# LED-Project.net
KiCad netlist of a schematic drawn in EAGLE
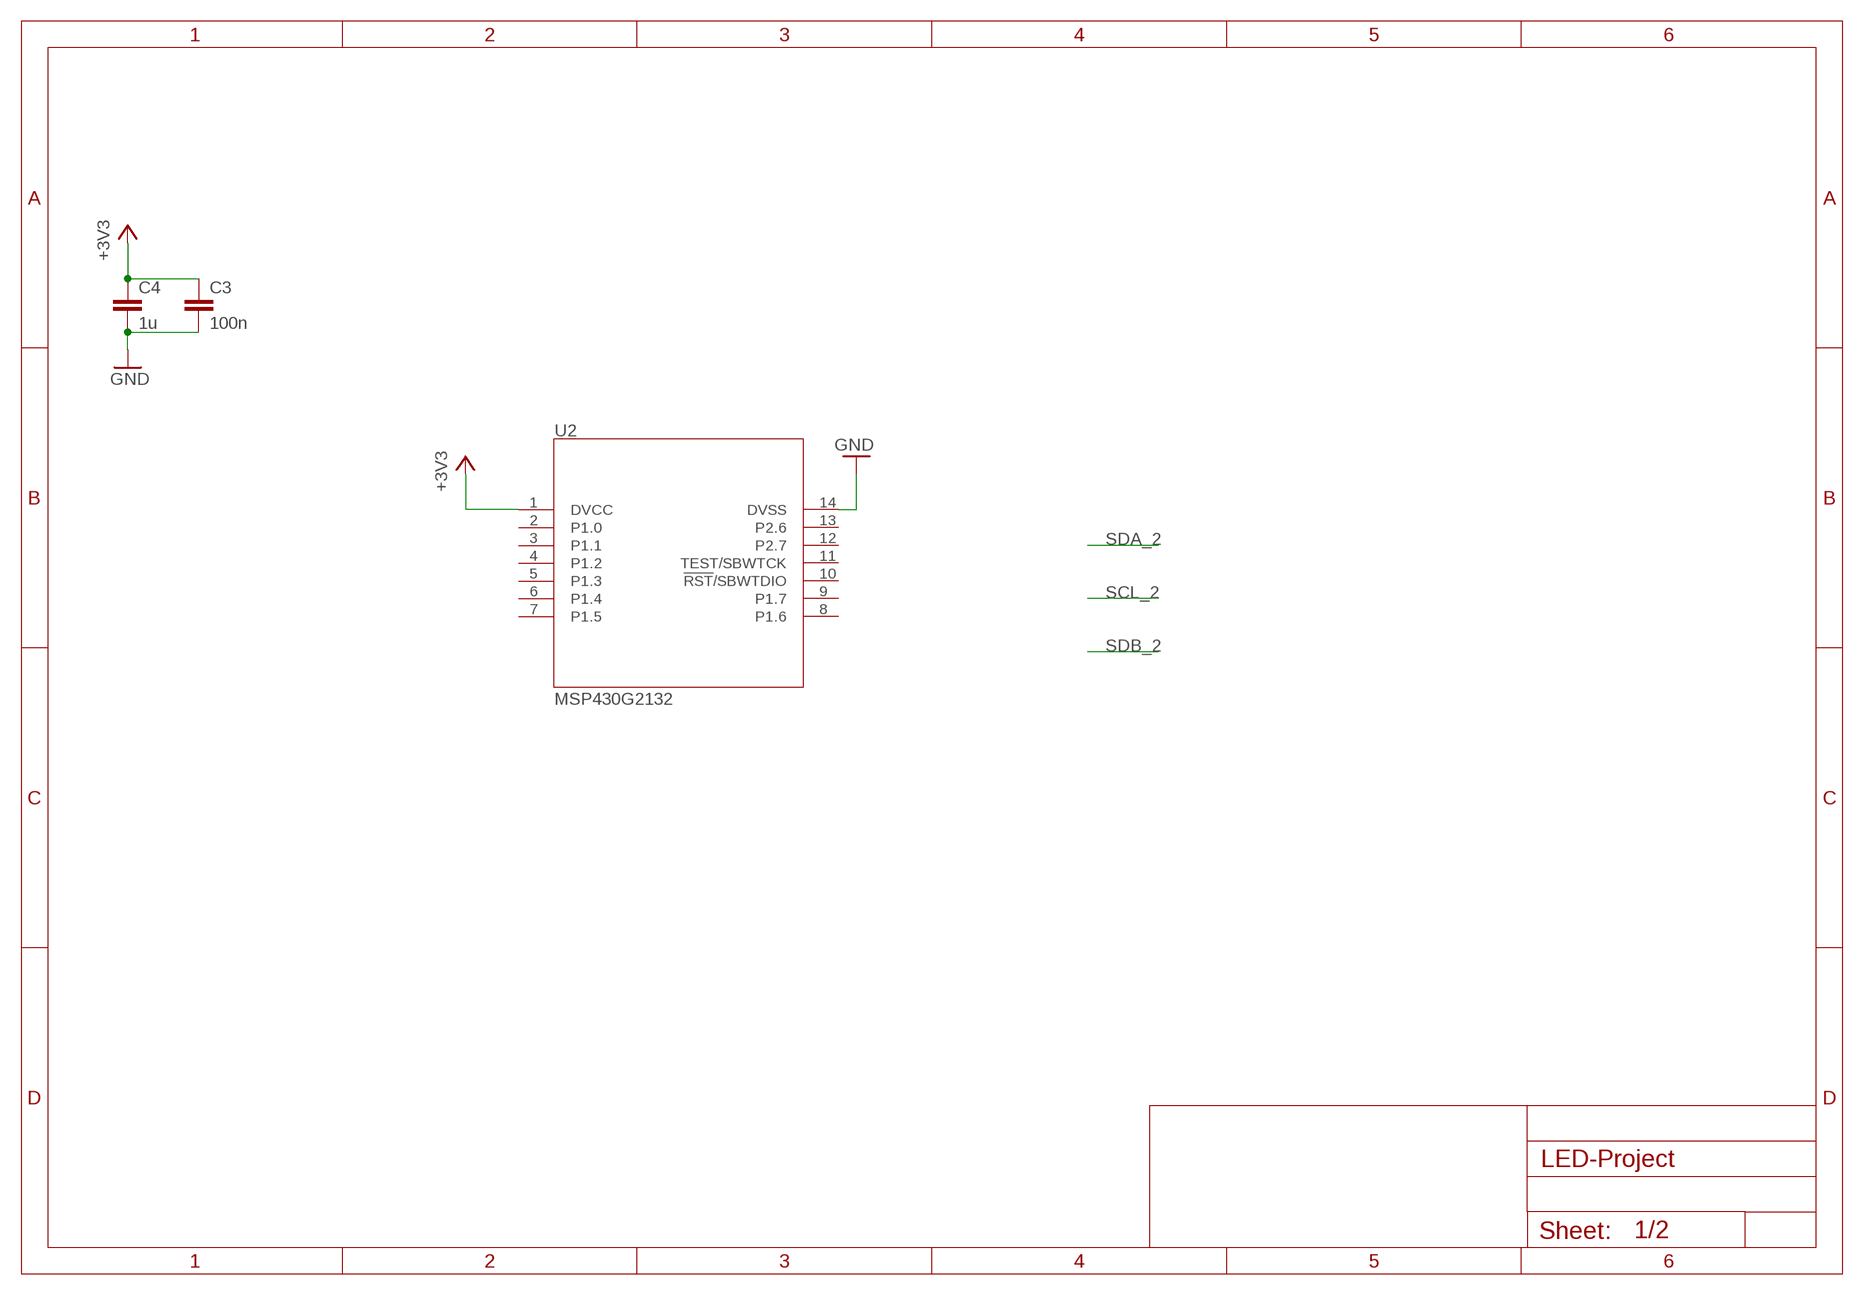
[diagram p0: schematic, sheet 1]
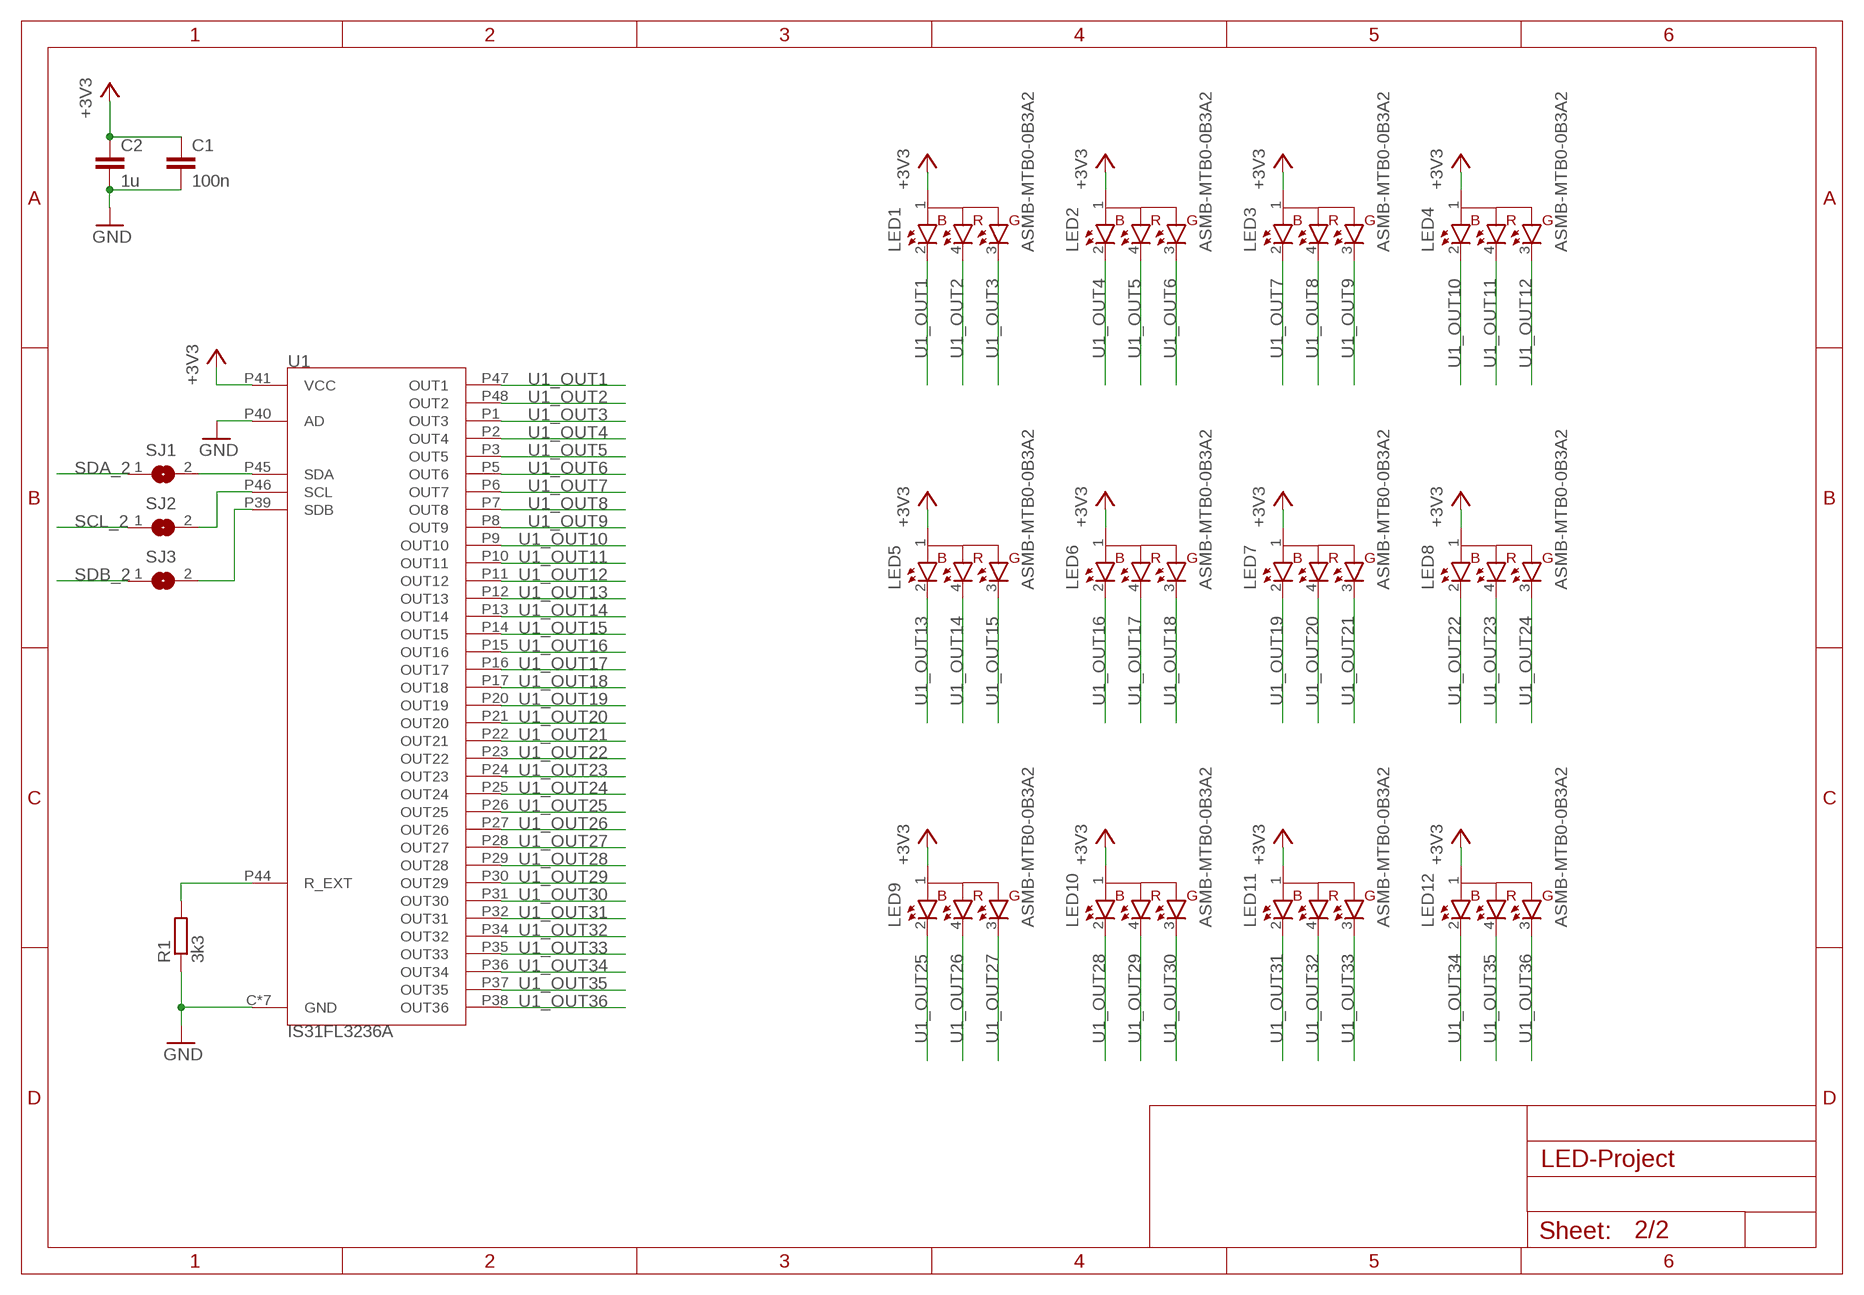
[diagram p1: schematic, sheet 2]

(export (version "E")
  (design (tool "Eeschema 10.0.6"))
  (components
    (comp (ref "C1")
      (value "100n")
      (footprint "eagle-import:C0805")
      (libsource (lib "eagle-import") (part "C-EUC0805"))
    )
    (comp (ref "C2")
      (value "1u")
      (footprint "eagle-import:C0805")
      (libsource (lib "eagle-import") (part "C-EUC0805"))
    )
    (comp (ref "LED1")
      (value "ASMB-MTB0-0B3A2")
      (footprint "eagle-import:LED-3.2-2.8")
      (libsource (lib "eagle-import") (part "ASMB-MTB0-0B3A2"))
    )
    (comp (ref "LED2")
      (value "ASMB-MTB0-0B3A2")
      (footprint "eagle-import:LED-3.2-2.8")
      (libsource (lib "eagle-import") (part "ASMB-MTB0-0B3A2"))
    )
    (comp (ref "LED3")
      (value "ASMB-MTB0-0B3A2")
      (footprint "eagle-import:LED-3.2-2.8")
      (libsource (lib "eagle-import") (part "ASMB-MTB0-0B3A2"))
    )
    (comp (ref "LED4")
      (value "ASMB-MTB0-0B3A2")
      (footprint "eagle-import:LED-3.2-2.8")
      (libsource (lib "eagle-import") (part "ASMB-MTB0-0B3A2"))
    )
    (comp (ref "LED5")
      (value "ASMB-MTB0-0B3A2")
      (footprint "eagle-import:LED-3.2-2.8")
      (libsource (lib "eagle-import") (part "ASMB-MTB0-0B3A2"))
    )
    (comp (ref "LED6")
      (value "ASMB-MTB0-0B3A2")
      (footprint "eagle-import:LED-3.2-2.8")
      (libsource (lib "eagle-import") (part "ASMB-MTB0-0B3A2"))
    )
    (comp (ref "LED7")
      (value "ASMB-MTB0-0B3A2")
      (footprint "eagle-import:LED-3.2-2.8")
      (libsource (lib "eagle-import") (part "ASMB-MTB0-0B3A2"))
    )
    (comp (ref "LED8")
      (value "ASMB-MTB0-0B3A2")
      (footprint "eagle-import:LED-3.2-2.8")
      (libsource (lib "eagle-import") (part "ASMB-MTB0-0B3A2"))
    )
    (comp (ref "LED9")
      (value "ASMB-MTB0-0B3A2")
      (footprint "eagle-import:LED-3.2-2.8")
      (libsource (lib "eagle-import") (part "ASMB-MTB0-0B3A2"))
    )
    (comp (ref "LED10")
      (value "ASMB-MTB0-0B3A2")
      (footprint "eagle-import:LED-3.2-2.8")
      (libsource (lib "eagle-import") (part "ASMB-MTB0-0B3A2"))
    )
    (comp (ref "LED11")
      (value "ASMB-MTB0-0B3A2")
      (footprint "eagle-import:LED-3.2-2.8")
      (libsource (lib "eagle-import") (part "ASMB-MTB0-0B3A2"))
    )
    (comp (ref "LED12")
      (value "ASMB-MTB0-0B3A2")
      (footprint "eagle-import:LED-3.2-2.8")
      (libsource (lib "eagle-import") (part "ASMB-MTB0-0B3A2"))
    )
    (comp (ref "R1")
      (value "3k3")
      (footprint "eagle-import:R0805")
      (libsource (lib "eagle-import") (part "R-EU_R0805"))
    )
    (comp (ref "SJ1") (value "SJ") (footprint "eagle-import:SJ") (libsource (lib "eagle-import") (part "SJ")))
    (comp (ref "SJ2") (value "SJ") (footprint "eagle-import:SJ") (libsource (lib "eagle-import") (part "SJ")))
    (comp (ref "SJ3") (value "SJ") (footprint "eagle-import:SJ") (libsource (lib "eagle-import") (part "SJ")))
    (comp (ref "U1")
      (value "IS31FL3236A")
      (footprint "eagle-import:ETQFP-48")
      (libsource (lib "eagle-import") (part "IS31FL3236A"))
    )
    (comp (ref "C3")
      (value "100n")
      (footprint "eagle-import:C0805")
      (libsource (lib "eagle-import") (part "C-EUC0805"))
    )
    (comp (ref "C4")
      (value "1u")
      (footprint "eagle-import:C0805")
      (libsource (lib "eagle-import") (part "C-EUC0805"))
    )
    (comp (ref "U2")
      (value "MSP430G2132")
      (footprint "eagle-import:TSSOP14")
      (libsource (lib "eagle-import") (part "MSP430G2132"))
    )
  )
  (nets
    (net (code "1") (name "+3V3") (class "Default")
      (node (ref "C1") (pin "1") (pinfunction "1_1") (pintype "passive"))
      (node (ref "C2") (pin "1") (pinfunction "1_1") (pintype "passive"))
      (node (ref "C3") (pin "1") (pinfunction "1_1") (pintype "passive"))
      (node (ref "C4") (pin "1") (pinfunction "1_1") (pintype "passive"))
      (node (ref "LED1") (pin "1") (pinfunction "P$1_1") (pintype "passive"))
      (node (ref "LED10") (pin "1") (pinfunction "P$1_1") (pintype "passive"))
      (node (ref "LED11") (pin "1") (pinfunction "P$1_1") (pintype "passive"))
      (node (ref "LED12") (pin "1") (pinfunction "P$1_1") (pintype "passive"))
      (node (ref "LED2") (pin "1") (pinfunction "P$1_1") (pintype "passive"))
      (node (ref "LED3") (pin "1") (pinfunction "P$1_1") (pintype "passive"))
      (node (ref "LED4") (pin "1") (pinfunction "P$1_1") (pintype "passive"))
      (node (ref "LED5") (pin "1") (pinfunction "P$1_1") (pintype "passive"))
      (node (ref "LED6") (pin "1") (pinfunction "P$1_1") (pintype "passive"))
      (node (ref "LED7") (pin "1") (pinfunction "P$1_1") (pintype "passive"))
      (node (ref "LED8") (pin "1") (pinfunction "P$1_1") (pintype "passive"))
      (node (ref "LED9") (pin "1") (pinfunction "P$1_1") (pintype "passive"))
      (node (ref "U1") (pin "P41") (pinfunction "VCC_P41") (pintype "bidirectional"))
      (node (ref "U2") (pin "1") (pinfunction "DVCC_1") (pintype "bidirectional"))
    )
    (net (code "2") (name "GND") (class "Default")
      (node (ref "C1") (pin "2") (pinfunction "2_2") (pintype "passive"))
      (node (ref "C2") (pin "2") (pinfunction "2_2") (pintype "passive"))
      (node (ref "C3") (pin "2") (pinfunction "2_2") (pintype "passive"))
      (node (ref "C4") (pin "2") (pinfunction "2_2") (pintype "passive"))
      (node (ref "R1") (pin "1") (pinfunction "1_1") (pintype "passive"))
      (node (ref "U1") (pin "C") (pinfunction "GND_C") (pintype "bidirectional"))
      (node (ref "U1") (pin "P18") (pinfunction "GND_P18") (pintype "bidirectional"))
      (node (ref "U1") (pin "P19") (pinfunction "GND_P19") (pintype "bidirectional"))
      (node (ref "U1") (pin "P33") (pinfunction "GND_P33") (pintype "bidirectional"))
      (node (ref "U1") (pin "P4") (pinfunction "GND_P4") (pintype "bidirectional"))
      (node (ref "U1") (pin "P40") (pinfunction "AD_P40") (pintype "bidirectional"))
      (node (ref "U1") (pin "P42") (pinfunction "GND_P42") (pintype "bidirectional"))
      (node (ref "U1") (pin "P43") (pinfunction "GND_P43") (pintype "bidirectional"))
      (node (ref "U2") (pin "14") (pinfunction "DVSS_14") (pintype "bidirectional"))
    )
    (net (code "3") (name "Net-(U1-R_EXT)") (class "Default")
      (node (ref "R1") (pin "2") (pinfunction "2_2") (pintype "passive"))
      (node (ref "U1") (pin "P44") (pinfunction "R_EXT_P44") (pintype "bidirectional"))
    )
    (net (code "4") (name "Net-(U1-SCL)") (class "Default")
      (node (ref "SJ2") (pin "2") (pinfunction "2_2") (pintype "passive"))
      (node (ref "U1") (pin "P46") (pinfunction "SCL_P46") (pintype "bidirectional"))
    )
    (net (code "5") (name "Net-(U1-SDA)") (class "Default")
      (node (ref "SJ1") (pin "2") (pinfunction "2_2") (pintype "passive"))
      (node (ref "U1") (pin "P45") (pinfunction "SDA_P45") (pintype "bidirectional"))
    )
    (net (code "6") (name "Net-(U1-SDB)") (class "Default")
      (node (ref "SJ3") (pin "2") (pinfunction "2_2") (pintype "passive"))
      (node (ref "U1") (pin "P39") (pinfunction "SDB_P39") (pintype "bidirectional"))
    )
    (net (code "7") (name "SCL_2") (class "Default")
      (node (ref "SJ2") (pin "1") (pinfunction "1_1") (pintype "passive"))
    )
    (net (code "8") (name "SDA_2") (class "Default")
      (node (ref "SJ1") (pin "1") (pinfunction "1_1") (pintype "passive"))
    )
    (net (code "9") (name "SDB_2") (class "Default")
      (node (ref "SJ3") (pin "1") (pinfunction "1_1") (pintype "passive"))
    )
    (net (code "10") (name "U1_OUT1") (class "Default")
      (node (ref "LED1") (pin "2") (pinfunction "BC_2") (pintype "passive"))
      (node (ref "U1") (pin "P47") (pinfunction "OUT1_P47") (pintype "bidirectional"))
    )
    (net (code "11") (name "U1_OUT2") (class "Default")
      (node (ref "LED1") (pin "4") (pinfunction "RC_4") (pintype "passive"))
      (node (ref "U1") (pin "P48") (pinfunction "OUT2_P48") (pintype "bidirectional"))
    )
    (net (code "12") (name "U1_OUT3") (class "Default")
      (node (ref "LED1") (pin "3") (pinfunction "GC_3") (pintype "passive"))
      (node (ref "U1") (pin "P1") (pinfunction "OUT3_P1") (pintype "bidirectional"))
    )
    (net (code "13") (name "U1_OUT4") (class "Default")
      (node (ref "LED2") (pin "2") (pinfunction "BC_2") (pintype "passive"))
      (node (ref "U1") (pin "P2") (pinfunction "OUT4_P2") (pintype "bidirectional"))
    )
    (net (code "14") (name "U1_OUT5") (class "Default")
      (node (ref "LED2") (pin "4") (pinfunction "RC_4") (pintype "passive"))
      (node (ref "U1") (pin "P3") (pinfunction "OUT5_P3") (pintype "bidirectional"))
    )
    (net (code "15") (name "U1_OUT6") (class "Default")
      (node (ref "LED2") (pin "3") (pinfunction "GC_3") (pintype "passive"))
      (node (ref "U1") (pin "P5") (pinfunction "OUT6_P5") (pintype "bidirectional"))
    )
    (net (code "16") (name "U1_OUT7") (class "Default")
      (node (ref "LED3") (pin "2") (pinfunction "BC_2") (pintype "passive"))
      (node (ref "U1") (pin "P6") (pinfunction "OUT7_P6") (pintype "bidirectional"))
    )
    (net (code "17") (name "U1_OUT8") (class "Default")
      (node (ref "LED3") (pin "4") (pinfunction "RC_4") (pintype "passive"))
      (node (ref "U1") (pin "P7") (pinfunction "OUT8_P7") (pintype "bidirectional"))
    )
    (net (code "18") (name "U1_OUT9") (class "Default")
      (node (ref "LED3") (pin "3") (pinfunction "GC_3") (pintype "passive"))
      (node (ref "U1") (pin "P8") (pinfunction "OUT9_P8") (pintype "bidirectional"))
    )
    (net (code "19") (name "U1_OUT10") (class "Default")
      (node (ref "LED4") (pin "2") (pinfunction "BC_2") (pintype "passive"))
      (node (ref "U1") (pin "P9") (pinfunction "OUT10_P9") (pintype "bidirectional"))
    )
    (net (code "20") (name "U1_OUT11") (class "Default")
      (node (ref "LED4") (pin "4") (pinfunction "RC_4") (pintype "passive"))
      (node (ref "U1") (pin "P10") (pinfunction "OUT11_P10") (pintype "bidirectional"))
    )
    (net (code "21") (name "U1_OUT12") (class "Default")
      (node (ref "LED4") (pin "3") (pinfunction "GC_3") (pintype "passive"))
      (node (ref "U1") (pin "P11") (pinfunction "OUT12_P11") (pintype "bidirectional"))
    )
    (net (code "22") (name "U1_OUT13") (class "Default")
      (node (ref "LED5") (pin "2") (pinfunction "BC_2") (pintype "passive"))
      (node (ref "U1") (pin "P12") (pinfunction "OUT13_P12") (pintype "bidirectional"))
    )
    (net (code "23") (name "U1_OUT14") (class "Default")
      (node (ref "LED5") (pin "4") (pinfunction "RC_4") (pintype "passive"))
      (node (ref "U1") (pin "P13") (pinfunction "OUT14_P13") (pintype "bidirectional"))
    )
    (net (code "24") (name "U1_OUT15") (class "Default")
      (node (ref "LED5") (pin "3") (pinfunction "GC_3") (pintype "passive"))
      (node (ref "U1") (pin "P14") (pinfunction "OUT15_P14") (pintype "bidirectional"))
    )
    (net (code "25") (name "U1_OUT16") (class "Default")
      (node (ref "LED6") (pin "2") (pinfunction "BC_2") (pintype "passive"))
      (node (ref "U1") (pin "P15") (pinfunction "OUT16_P15") (pintype "bidirectional"))
    )
    (net (code "26") (name "U1_OUT17") (class "Default")
      (node (ref "LED6") (pin "4") (pinfunction "RC_4") (pintype "passive"))
      (node (ref "U1") (pin "P16") (pinfunction "OUT17_P16") (pintype "bidirectional"))
    )
    (net (code "27") (name "U1_OUT18") (class "Default")
      (node (ref "LED6") (pin "3") (pinfunction "GC_3") (pintype "passive"))
      (node (ref "U1") (pin "P17") (pinfunction "OUT18_P17") (pintype "bidirectional"))
    )
    (net (code "28") (name "U1_OUT19") (class "Default")
      (node (ref "LED7") (pin "2") (pinfunction "BC_2") (pintype "passive"))
      (node (ref "U1") (pin "P20") (pinfunction "OUT19_P20") (pintype "bidirectional"))
    )
    (net (code "29") (name "U1_OUT20") (class "Default")
      (node (ref "LED7") (pin "4") (pinfunction "RC_4") (pintype "passive"))
      (node (ref "U1") (pin "P21") (pinfunction "OUT20_P21") (pintype "bidirectional"))
    )
    (net (code "30") (name "U1_OUT21") (class "Default")
      (node (ref "LED7") (pin "3") (pinfunction "GC_3") (pintype "passive"))
      (node (ref "U1") (pin "P22") (pinfunction "OUT21_P22") (pintype "bidirectional"))
    )
    (net (code "31") (name "U1_OUT22") (class "Default")
      (node (ref "LED8") (pin "2") (pinfunction "BC_2") (pintype "passive"))
      (node (ref "U1") (pin "P23") (pinfunction "OUT22_P23") (pintype "bidirectional"))
    )
    (net (code "32") (name "U1_OUT23") (class "Default")
      (node (ref "LED8") (pin "4") (pinfunction "RC_4") (pintype "passive"))
      (node (ref "U1") (pin "P24") (pinfunction "OUT23_P24") (pintype "bidirectional"))
    )
    (net (code "33") (name "U1_OUT24") (class "Default")
      (node (ref "LED8") (pin "3") (pinfunction "GC_3") (pintype "passive"))
      (node (ref "U1") (pin "P25") (pinfunction "OUT24_P25") (pintype "bidirectional"))
    )
    (net (code "34") (name "U1_OUT25") (class "Default")
      (node (ref "LED9") (pin "2") (pinfunction "BC_2") (pintype "passive"))
      (node (ref "U1") (pin "P26") (pinfunction "OUT25_P26") (pintype "bidirectional"))
    )
    (net (code "35") (name "U1_OUT26") (class "Default")
      (node (ref "LED9") (pin "4") (pinfunction "RC_4") (pintype "passive"))
      (node (ref "U1") (pin "P27") (pinfunction "OUT26_P27") (pintype "bidirectional"))
    )
    (net (code "36") (name "U1_OUT27") (class "Default")
      (node (ref "LED9") (pin "3") (pinfunction "GC_3") (pintype "passive"))
      (node (ref "U1") (pin "P28") (pinfunction "OUT27_P28") (pintype "bidirectional"))
    )
    (net (code "37") (name "U1_OUT28") (class "Default")
      (node (ref "LED10") (pin "2") (pinfunction "BC_2") (pintype "passive"))
      (node (ref "U1") (pin "P29") (pinfunction "OUT28_P29") (pintype "bidirectional"))
    )
    (net (code "38") (name "U1_OUT29") (class "Default")
      (node (ref "LED10") (pin "4") (pinfunction "RC_4") (pintype "passive"))
      (node (ref "U1") (pin "P30") (pinfunction "OUT29_P30") (pintype "bidirectional"))
    )
    (net (code "39") (name "U1_OUT30") (class "Default")
      (node (ref "LED10") (pin "3") (pinfunction "GC_3") (pintype "passive"))
      (node (ref "U1") (pin "P31") (pinfunction "OUT30_P31") (pintype "bidirectional"))
    )
    (net (code "40") (name "U1_OUT31") (class "Default")
      (node (ref "LED11") (pin "2") (pinfunction "BC_2") (pintype "passive"))
      (node (ref "U1") (pin "P32") (pinfunction "OUT31_P32") (pintype "bidirectional"))
    )
    (net (code "41") (name "U1_OUT32") (class "Default")
      (node (ref "LED11") (pin "4") (pinfunction "RC_4") (pintype "passive"))
      (node (ref "U1") (pin "P34") (pinfunction "OUT32_P34") (pintype "bidirectional"))
    )
    (net (code "42") (name "U1_OUT33") (class "Default")
      (node (ref "LED11") (pin "3") (pinfunction "GC_3") (pintype "passive"))
      (node (ref "U1") (pin "P35") (pinfunction "OUT33_P35") (pintype "bidirectional"))
    )
    (net (code "43") (name "U1_OUT34") (class "Default")
      (node (ref "LED12") (pin "2") (pinfunction "BC_2") (pintype "passive"))
      (node (ref "U1") (pin "P36") (pinfunction "OUT34_P36") (pintype "bidirectional"))
    )
    (net (code "44") (name "U1_OUT35") (class "Default")
      (node (ref "LED12") (pin "4") (pinfunction "RC_4") (pintype "passive"))
      (node (ref "U1") (pin "P37") (pinfunction "OUT35_P37") (pintype "bidirectional"))
    )
    (net (code "45") (name "U1_OUT36") (class "Default")
      (node (ref "LED12") (pin "3") (pinfunction "GC_3") (pintype "passive"))
      (node (ref "U1") (pin "P38") (pinfunction "OUT36_P38") (pintype "bidirectional"))
    )
    (net (code "46") (name "unconnected-(U2-P1.0-Pad2)") (class "Default")
      (node (ref "U2") (pin "2") (pinfunction "P1.0_2") (pintype "bidirectional"))
    )
    (net (code "47") (name "unconnected-(U2-P1.1-Pad3)") (class "Default")
      (node (ref "U2") (pin "3") (pinfunction "P1.1_3") (pintype "bidirectional"))
    )
    (net (code "48") (name "unconnected-(U2-P1.2-Pad4)") (class "Default")
      (node (ref "U2") (pin "4") (pinfunction "P1.2_4") (pintype "bidirectional"))
    )
    (net (code "49") (name "unconnected-(U2-P1.3-Pad5)") (class "Default")
      (node (ref "U2") (pin "5") (pinfunction "P1.3_5") (pintype "bidirectional"))
    )
    (net (code "50") (name "unconnected-(U2-P1.4-Pad6)") (class "Default")
      (node (ref "U2") (pin "6") (pinfunction "P1.4_6") (pintype "bidirectional"))
    )
    (net (code "51") (name "unconnected-(U2-P1.5-Pad7)") (class "Default")
      (node (ref "U2") (pin "7") (pinfunction "P1.5_7") (pintype "bidirectional"))
    )
    (net (code "52") (name "unconnected-(U2-P1.6-Pad8)") (class "Default")
      (node (ref "U2") (pin "8") (pinfunction "P1.6_8") (pintype "bidirectional"))
    )
    (net (code "53") (name "unconnected-(U2-P1.7-Pad9)") (class "Default")
      (node (ref "U2") (pin "9") (pinfunction "P1.7_9") (pintype "bidirectional"))
    )
    (net (code "54") (name "unconnected-(U2-P2.6-Pad13)") (class "Default")
      (node (ref "U2") (pin "13") (pinfunction "P2.6_13") (pintype "bidirectional"))
    )
    (net (code "55") (name "unconnected-(U2-P2.7-Pad12)") (class "Default")
      (node (ref "U2") (pin "12") (pinfunction "P2.7_12") (pintype "bidirectional"))
    )
    (net (code "56") (name "unconnected-(U2-TEST{slash}SBWTCK-Pad11)") (class "Default")
      (node (ref "U2") (pin "11") (pinfunction "TEST/SBWTCK_11") (pintype "bidirectional"))
    )
    (net (code "57") (name "unconnected-(U2-~{RST}{slash}SBWTDIO-Pad10)") (class "Default")
      (node (ref "U2") (pin "10") (pinfunction "~{RST}/SBWTDIO_10") (pintype "bidirectional"))
    )
  )
)
